# Power.net
KiCad netlist of a schematic drawn in Altium Designer
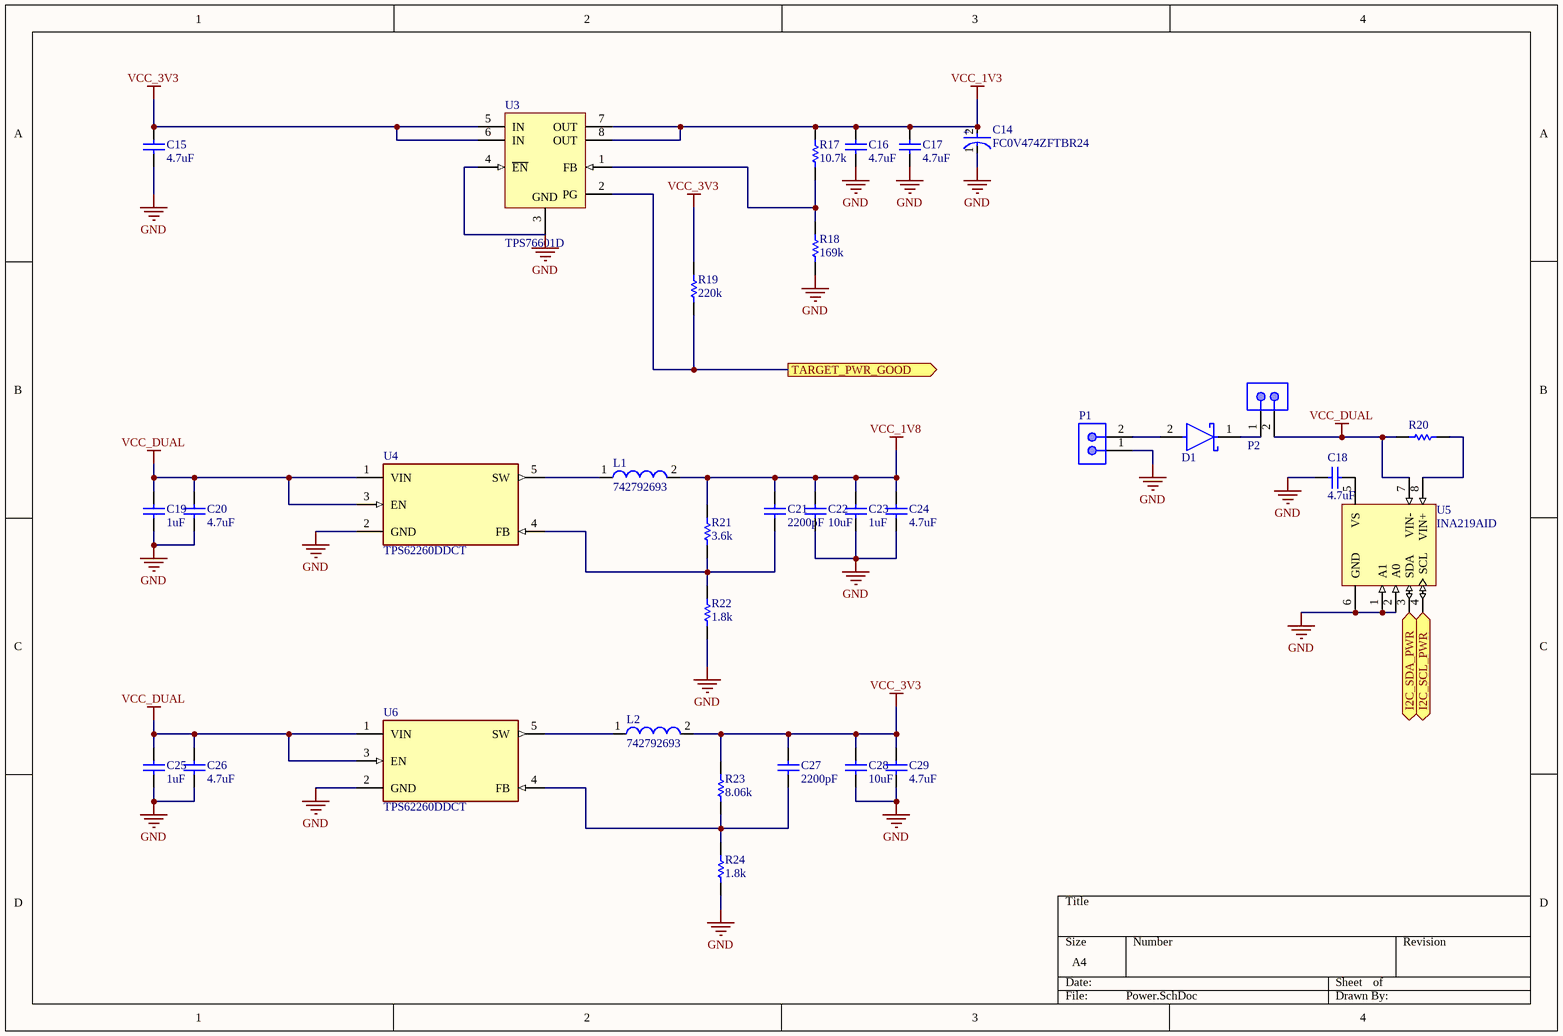
[diagram p0: Power.SchDoc]

(export (version "E")
  (design (tool "Eeschema 10.0.6"))
  (components
    (comp (ref "C14")
      (value "FC0V474ZFTBR24")
      (footprint "FP-FC0V474ZFTBR24-MFG")
      (description "CAP 470MF -20% +80% 3.5V SMD")
      (fields (field (name "TOLERANCE") "80%") (field (name "VOLTAGE") "3.5V"))
      (libsource (lib "Altium Content Vault") (part "a00bbbee19879c290e62620ae7e47b1"))
    )
    (comp (ref "C15")
      (value "4.7uF")
      (footprint "0805_C_S")
      (description "Capacitor")
      (fields (field (name "PUBLISHER") "Altium Limited"))
      (libsource (lib "Miscellaneous Devices") (part "Cap"))
    )
    (comp (ref "C16")
      (value "4.7uF")
      (footprint "0805_C_S")
      (description "Capacitor")
      (fields (field (name "PUBLISHER") "Altium Limited"))
      (libsource (lib "Miscellaneous Devices") (part "Cap"))
    )
    (comp (ref "C17")
      (value "4.7uF")
      (footprint "0805_C_S")
      (description "Capacitor")
      (fields (field (name "PUBLISHER") "Altium Limited"))
      (libsource (lib "Miscellaneous Devices") (part "Cap"))
    )
    (comp (ref "C18")
      (value "4.7uF")
      (footprint "0805_C_S")
      (description "Capacitor")
      (fields (field (name "PUBLISHER") "Altium Limited"))
      (libsource (lib "Miscellaneous Devices") (part "Cap"))
    )
    (comp (ref "C19")
      (value "1uF")
      (footprint "0805_C_S")
      (description "Capacitor")
      (fields (field (name "PUBLISHER") "Altium Limited"))
      (libsource (lib "Miscellaneous Devices") (part "Cap"))
    )
    (comp (ref "C20")
      (value "4.7uF")
      (footprint "0805_C_S")
      (description "Capacitor")
      (fields (field (name "PUBLISHER") "Altium Limited"))
      (libsource (lib "Miscellaneous Devices") (part "Cap"))
    )
    (comp (ref "C21")
      (value "2200pF")
      (footprint "0805_C_S")
      (description "Capacitor")
      (fields (field (name "PUBLISHER") "Altium Limited"))
      (libsource (lib "Miscellaneous Devices") (part "Cap"))
    )
    (comp (ref "C22")
      (value "10uF")
      (footprint "0805_C_S")
      (description "Capacitor")
      (fields (field (name "PUBLISHER") "Altium Limited"))
      (libsource (lib "Miscellaneous Devices") (part "Cap"))
    )
    (comp (ref "C23")
      (value "1uF")
      (footprint "0805_C_S")
      (description "Capacitor")
      (fields (field (name "PUBLISHER") "Altium Limited"))
      (libsource (lib "Miscellaneous Devices") (part "Cap"))
    )
    (comp (ref "C24")
      (value "4.7uF")
      (footprint "0805_C_S")
      (description "Capacitor")
      (fields (field (name "PUBLISHER") "Altium Limited"))
      (libsource (lib "Miscellaneous Devices") (part "Cap"))
    )
    (comp (ref "C25")
      (value "1uF")
      (footprint "0805_C_S")
      (description "Capacitor")
      (fields (field (name "PUBLISHER") "Altium Limited"))
      (libsource (lib "Miscellaneous Devices") (part "Cap"))
    )
    (comp (ref "C26")
      (value "4.7uF")
      (footprint "0805_C_S")
      (description "Capacitor")
      (fields (field (name "PUBLISHER") "Altium Limited"))
      (libsource (lib "Miscellaneous Devices") (part "Cap"))
    )
    (comp (ref "C27")
      (value "2200pF")
      (footprint "0805_C_S")
      (description "Capacitor")
      (fields (field (name "PUBLISHER") "Altium Limited"))
      (libsource (lib "Miscellaneous Devices") (part "Cap"))
    )
    (comp (ref "C28")
      (value "10uF")
      (footprint "0805_C_S")
      (description "Capacitor")
      (fields (field (name "PUBLISHER") "Altium Limited"))
      (libsource (lib "Miscellaneous Devices") (part "Cap"))
    )
    (comp (ref "C29")
      (value "4.7uF")
      (footprint "0805_C_S")
      (description "Capacitor")
      (fields (field (name "PUBLISHER") "Altium Limited"))
      (libsource (lib "Miscellaneous Devices") (part "Cap"))
    )
    (comp (ref "D1")
      (value "MBR0520LT1G")
      (footprint "FP-425-04-IPC_C")
      (description "DIODE SCHOTTKY 20V 500MA SOD123")
      (libsource (lib "Altium Content Vault") (part "1d6ec82d83fb6aee721767c19dac4b9"))
    )
    (comp (ref "L1")
      (value "742792693")
      (footprint "SMD-0603")
      (description "SMD EMI Suppression Ferrite Bead WE-CBF, Z = 2200 Ohm")
      (libsource (lib "Altium Content Vault") (part "PAS-IND-INDUCTOR-2"))
    )
    (comp (ref "L2")
      (value "742792693")
      (footprint "SMD-0603")
      (description "SMD EMI Suppression Ferrite Bead WE-CBF, Z = 2200 Ohm")
      (libsource (lib "Altium Content Vault") (part "PAS-IND-INDUCTOR-2"))
    )
    (comp (ref "P1")
      (value "22-23-2021")
      (footprint "MOLX-22-23-2021_V")
      (libsource (lib "") (part "CN-1P-M-R2_1"))
    )
    (comp (ref "P2")
      (value "22-23-2021")
      (footprint "MOLX-22-23-2021_V")
      (libsource (lib "Altium Content Vault") (part "CN-1P-M-R2"))
    )
    (comp (ref "R17")
      (value "10.7k")
      (footprint "0805_R_S")
      (description "Resistor")
      (fields (field (name "PUBLISHER") "Altium Limited"))
      (libsource (lib "Miscellaneous Devices") (part "Res1"))
    )
    (comp (ref "R18")
      (value "169k")
      (footprint "0805_R_S")
      (description "Resistor")
      (fields (field (name "PUBLISHER") "Altium Limited"))
      (libsource (lib "Miscellaneous Devices") (part "Res1"))
    )
    (comp (ref "R19")
      (value "220k")
      (footprint "0805_R_S")
      (description "Resistor")
      (fields (field (name "PUBLISHER") "Altium Limited"))
      (libsource (lib "Miscellaneous Devices") (part "Res1"))
    )
    (comp (ref "R20")
      (value "ERJ-6GEYJ1R0V")
      (footprint "RESC2013X70X40NL20T20")
      (fields (field (name "MANUFACTURER") "Panasonic"))
      (libsource (lib "Altium Content Vault") (part "RES"))
    )
    (comp (ref "R21")
      (value "3.6k")
      (footprint "0805_R_S")
      (description "Resistor")
      (fields (field (name "PUBLISHER") "Altium Limited"))
      (libsource (lib "Miscellaneous Devices") (part "Res1"))
    )
    (comp (ref "R22")
      (value "1.8k")
      (footprint "0805_R_S")
      (description "Resistor")
      (fields (field (name "PUBLISHER") "Altium Limited"))
      (libsource (lib "Miscellaneous Devices") (part "Res1"))
    )
    (comp (ref "R23")
      (value "8.06k")
      (footprint "0805_R_S")
      (description "Resistor")
      (fields (field (name "PUBLISHER") "Altium Limited"))
      (libsource (lib "Miscellaneous Devices") (part "Res1"))
    )
    (comp (ref "R24")
      (value "1.8k")
      (footprint "0805_R_S")
      (description "Resistor")
      (fields (field (name "PUBLISHER") "Altium Limited"))
      (libsource (lib "Miscellaneous Devices") (part "Res1"))
    )
    (comp (ref "U3")
      (value "TPS76601D")
      (footprint "D0008A_N")
      (fields (field (name "MANUFACTURER") "Texas Instruments"))
      (libsource (lib "Altium Content Vault") (part "TI-TPS76X01D8"))
    )
    (comp (ref "U4")
      (value "TPS62260DDCT")
      (footprint "FP-DDC0005A-MFG")
      (description "IC REG BUCK ADJ 600MA SOT23-5")
      (libsource (lib "Altium Content Vault") (part "570bdd5f8c63060c83363458e000459"))
    )
    (comp (ref "U5")
      (value "INA219AID")
      (footprint "D0008A_N")
      (fields (field (name "MANUFACTURER") "Texas Instruments"))
      (libsource (lib "Altium Content Vault") (part "TI-INA219D8"))
    )
    (comp (ref "U6")
      (value "TPS62260DDCT")
      (footprint "FP-DDC0005A-MFG")
      (description "IC REG BUCK ADJ 600MA SOT23-5")
      (libsource (lib "Altium Content Vault") (part "570bdd5f8c63060c83363458e000459"))
    )
  )
  (nets
    (net (code "1") (name "/I2C_SCL_PWR") (class "Default")
      (node (ref "U5") (pin "4") (pinfunction "SCL_4") (pintype "bidirectional"))
    )
    (net (code "2") (name "/I2C_SDA_PWR") (class "Default")
      (node (ref "U5") (pin "3") (pinfunction "SDA_3") (pintype "bidirectional"))
    )
    (net (code "3") (name "/TARGET_PWR_GOOD") (class "Default")
      (node (ref "R19") (pin "2") (pinfunction "2_2") (pintype "passive"))
      (node (ref "U3") (pin "2") (pinfunction "PG_2") (pintype "tri_state"))
    )
    (net (code "4") (name "GND") (class "Default")
      (node (ref "C14") (pin "1") (pinfunction "C_1") (pintype "passive"))
      (node (ref "C15") (pin "1") (pinfunction "1_1") (pintype "passive"))
      (node (ref "C16") (pin "1") (pinfunction "1_1") (pintype "passive"))
      (node (ref "C17") (pin "1") (pinfunction "1_1") (pintype "passive"))
      (node (ref "C18") (pin "2") (pinfunction "2_2") (pintype "passive"))
      (node (ref "C19") (pin "1") (pinfunction "1_1") (pintype "passive"))
      (node (ref "C20") (pin "1") (pinfunction "1_1") (pintype "passive"))
      (node (ref "C22") (pin "1") (pinfunction "1_1") (pintype "passive"))
      (node (ref "C23") (pin "1") (pinfunction "1_1") (pintype "passive"))
      (node (ref "C24") (pin "1") (pinfunction "1_1") (pintype "passive"))
      (node (ref "C25") (pin "1") (pinfunction "1_1") (pintype "passive"))
      (node (ref "C26") (pin "1") (pinfunction "1_1") (pintype "passive"))
      (node (ref "C28") (pin "1") (pinfunction "1_1") (pintype "passive"))
      (node (ref "C29") (pin "1") (pinfunction "1_1") (pintype "passive"))
      (node (ref "P1") (pin "1") (pinfunction "1_1") (pintype "passive"))
      (node (ref "R18") (pin "2") (pinfunction "2_2") (pintype "passive"))
      (node (ref "R22") (pin "2") (pinfunction "2_2") (pintype "passive"))
      (node (ref "R24") (pin "2") (pinfunction "2_2") (pintype "passive"))
      (node (ref "U3") (pin "4") (pinfunction "~{EN}_4") (pintype "input"))
      (node (ref "U4") (pin "2") (pinfunction "GND_2") (pintype "power_in"))
      (node (ref "U5") (pin "1") (pinfunction "A1_1") (pintype "input"))
      (node (ref "U5") (pin "2") (pinfunction "A0_2") (pintype "input"))
      (node (ref "U5") (pin "6") (pinfunction "GND_6") (pintype "power_in"))
      (node (ref "U6") (pin "2") (pinfunction "GND_2") (pintype "power_in"))
    )
    (net (code "5") (name "Net-(D1-A)") (class "Default")
      (node (ref "D1") (pin "2") (pinfunction "A_2") (pintype "passive"))
      (node (ref "P1") (pin "2") (pinfunction "2_2") (pintype "passive"))
    )
    (net (code "6") (name "Net-(D1-C)") (class "Default")
      (node (ref "D1") (pin "1") (pinfunction "C_1") (pintype "passive"))
      (node (ref "P2") (pin "1") (pinfunction "1_1") (pintype "passive"))
    )
    (net (code "7") (name "Net-(U3-FB)") (class "Default")
      (node (ref "R17") (pin "2") (pinfunction "2_2") (pintype "passive"))
      (node (ref "R18") (pin "1") (pinfunction "1_1") (pintype "passive"))
      (node (ref "U3") (pin "1") (pinfunction "FB_1") (pintype "input"))
    )
    (net (code "8") (name "Net-(U4-FB)") (class "Default")
      (node (ref "C21") (pin "1") (pinfunction "1_1") (pintype "passive"))
      (node (ref "R21") (pin "2") (pinfunction "2_2") (pintype "passive"))
      (node (ref "R22") (pin "1") (pinfunction "1_1") (pintype "passive"))
      (node (ref "U4") (pin "4") (pinfunction "FB_4") (pintype "input"))
    )
    (net (code "9") (name "Net-(U4-SW)") (class "Default")
      (node (ref "L1") (pin "1") (pinfunction "1_1") (pintype "passive"))
      (node (ref "U4") (pin "5") (pinfunction "SW_5") (pintype "output"))
    )
    (net (code "10") (name "Net-(U5-VIN+)") (class "Default")
      (node (ref "R20") (pin "2") (pinfunction "2_2") (pintype "passive"))
      (node (ref "U5") (pin "8") (pinfunction "VIN+_8") (pintype "input"))
    )
    (net (code "11") (name "Net-(U5-VS)") (class "Default")
      (node (ref "C18") (pin "1") (pinfunction "1_1") (pintype "passive"))
      (node (ref "U5") (pin "5") (pinfunction "VS_5") (pintype "power_in"))
    )
    (net (code "12") (name "Net-(U6-FB)") (class "Default")
      (node (ref "C27") (pin "1") (pinfunction "1_1") (pintype "passive"))
      (node (ref "R23") (pin "2") (pinfunction "2_2") (pintype "passive"))
      (node (ref "R24") (pin "1") (pinfunction "1_1") (pintype "passive"))
      (node (ref "U6") (pin "4") (pinfunction "FB_4") (pintype "input"))
    )
    (net (code "13") (name "Net-(U6-SW)") (class "Default")
      (node (ref "L2") (pin "1") (pinfunction "1_1") (pintype "passive"))
      (node (ref "U6") (pin "5") (pinfunction "SW_5") (pintype "output"))
    )
    (net (code "14") (name "VCC_1V3") (class "Default")
      (node (ref "C14") (pin "2") (pinfunction "A_2") (pintype "passive"))
      (node (ref "C16") (pin "2") (pinfunction "2_2") (pintype "passive"))
      (node (ref "C17") (pin "2") (pinfunction "2_2") (pintype "passive"))
      (node (ref "R17") (pin "1") (pinfunction "1_1") (pintype "passive"))
      (node (ref "U3") (pin "7") (pinfunction "OUT_7") (pintype "power_in"))
      (node (ref "U3") (pin "8") (pinfunction "OUT_8") (pintype "power_in"))
    )
    (net (code "15") (name "VCC_1V8") (class "Default")
      (node (ref "C21") (pin "2") (pinfunction "2_2") (pintype "passive"))
      (node (ref "C22") (pin "2") (pinfunction "2_2") (pintype "passive"))
      (node (ref "C23") (pin "2") (pinfunction "2_2") (pintype "passive"))
      (node (ref "C24") (pin "2") (pinfunction "2_2") (pintype "passive"))
      (node (ref "L1") (pin "2") (pinfunction "2_2") (pintype "passive"))
      (node (ref "R21") (pin "1") (pinfunction "1_1") (pintype "passive"))
    )
    (net (code "16") (name "VCC_3V3") (class "Default")
      (node (ref "C15") (pin "2") (pinfunction "2_2") (pintype "passive"))
      (node (ref "C27") (pin "2") (pinfunction "2_2") (pintype "passive"))
      (node (ref "C28") (pin "2") (pinfunction "2_2") (pintype "passive"))
      (node (ref "C29") (pin "2") (pinfunction "2_2") (pintype "passive"))
      (node (ref "L2") (pin "2") (pinfunction "2_2") (pintype "passive"))
      (node (ref "R19") (pin "1") (pinfunction "1_1") (pintype "passive"))
      (node (ref "R23") (pin "1") (pinfunction "1_1") (pintype "passive"))
      (node (ref "U3") (pin "5") (pinfunction "IN_5") (pintype "power_in"))
      (node (ref "U3") (pin "6") (pinfunction "IN_6") (pintype "power_in"))
    )
    (net (code "17") (name "VCC_DUAL") (class "Default")
      (node (ref "C19") (pin "2") (pinfunction "2_2") (pintype "passive"))
      (node (ref "C20") (pin "2") (pinfunction "2_2") (pintype "passive"))
      (node (ref "C25") (pin "2") (pinfunction "2_2") (pintype "passive"))
      (node (ref "C26") (pin "2") (pinfunction "2_2") (pintype "passive"))
      (node (ref "P2") (pin "2") (pinfunction "2_2") (pintype "passive"))
      (node (ref "R20") (pin "1") (pinfunction "1_1") (pintype "passive"))
      (node (ref "U4") (pin "1") (pinfunction "VIN_1") (pintype "power_in"))
      (node (ref "U4") (pin "3") (pinfunction "EN_3") (pintype "input"))
      (node (ref "U5") (pin "7") (pinfunction "VIN-_7") (pintype "input"))
      (node (ref "U6") (pin "1") (pinfunction "VIN_1") (pintype "power_in"))
      (node (ref "U6") (pin "3") (pinfunction "EN_3") (pintype "input"))
    )
    (net (code "18") (name "unconnected-(U3-GND-Pad3)") (class "Default")
      (node (ref "U3") (pin "3") (pinfunction "GND_3") (pintype "power_in"))
    )
  )
)
